# adc_dac_main6.net
KiCad netlist of a schematic drawn in Altium Designer
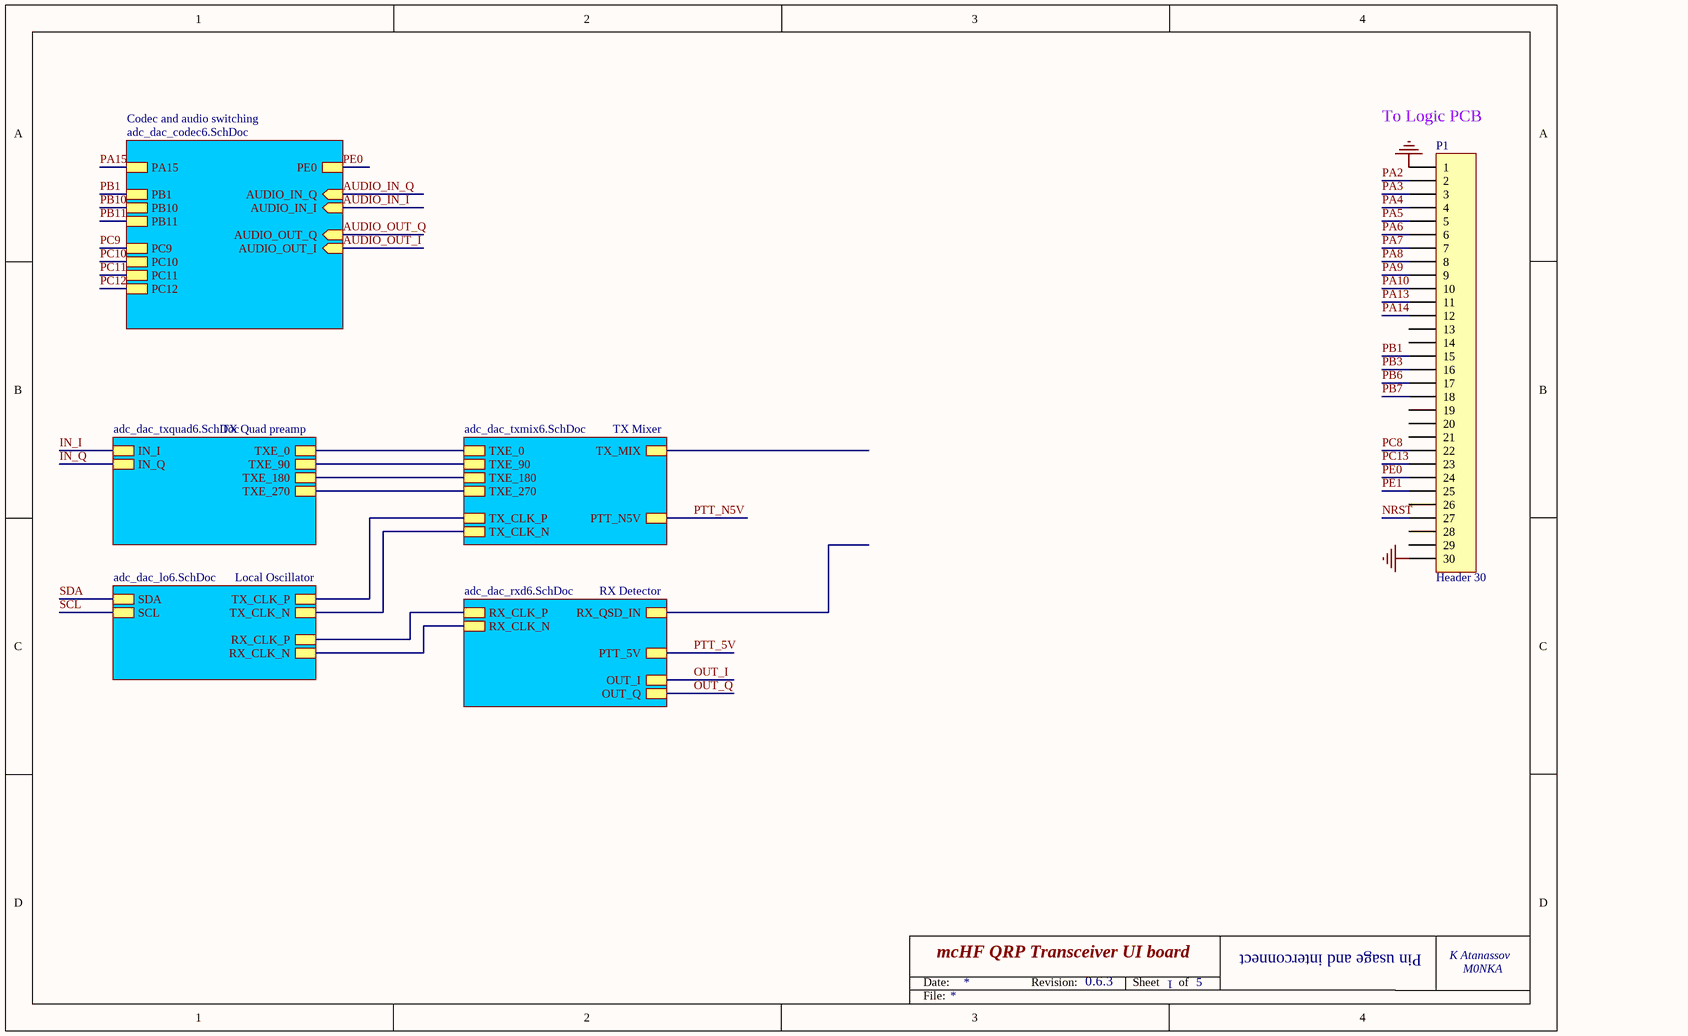
[diagram p0: adc_dac_main6.SchDoc]

(export (version "E")
  (design (tool "Eeschema 10.0.6"))
  (components
    (comp (ref "P1")
      (value "Header 30")
      (footprint "HDR1X30")
      (description "Header, 30-Pin")
      (libsource (lib "mcHF_ui") (part "Header 30"))
    )
  )
  (nets
    (net (code "7") (name "/NRST") (class "Default")
      (node (ref "P1") (pin "27") (pinfunction "27_27") (pintype "passive"))
    )
    (net (code "10") (name "/PA2") (class "Default")
      (node (ref "P1") (pin "2") (pinfunction "2_2") (pintype "passive"))
    )
    (net (code "11") (name "/PA3") (class "Default")
      (node (ref "P1") (pin "3") (pinfunction "3_3") (pintype "passive"))
    )
    (net (code "12") (name "/PA4") (class "Default")
      (node (ref "P1") (pin "4") (pinfunction "4_4") (pintype "passive"))
    )
    (net (code "13") (name "/PA5") (class "Default")
      (node (ref "P1") (pin "5") (pinfunction "5_5") (pintype "passive"))
    )
    (net (code "14") (name "/PA6") (class "Default")
      (node (ref "P1") (pin "6") (pinfunction "6_6") (pintype "passive"))
    )
    (net (code "15") (name "/PA7") (class "Default")
      (node (ref "P1") (pin "7") (pinfunction "7_7") (pintype "passive"))
    )
    (net (code "16") (name "/PA8") (class "Default")
      (node (ref "P1") (pin "8") (pinfunction "8_8") (pintype "passive"))
    )
    (net (code "17") (name "/PA9") (class "Default")
      (node (ref "P1") (pin "9") (pinfunction "9_9") (pintype "passive"))
    )
    (net (code "18") (name "/PA10") (class "Default")
      (node (ref "P1") (pin "10") (pinfunction "10_10") (pintype "passive"))
    )
    (net (code "19") (name "/PA13") (class "Default")
      (node (ref "P1") (pin "11") (pinfunction "11_11") (pintype "passive"))
    )
    (net (code "20") (name "/PA14") (class "Default")
      (node (ref "P1") (pin "12") (pinfunction "12_12") (pintype "passive"))
    )
    (net (code "22") (name "/PB1") (class "Default")
      (node (ref "P1") (pin "15") (pinfunction "15_15") (pintype "passive"))
    )
    (net (code "23") (name "/PB3") (class "Default")
      (node (ref "P1") (pin "16") (pinfunction "16_16") (pintype "passive"))
    )
    (net (code "24") (name "/PB6") (class "Default")
      (node (ref "P1") (pin "17") (pinfunction "17_17") (pintype "passive"))
    )
    (net (code "25") (name "/PB7") (class "Default")
      (node (ref "P1") (pin "18") (pinfunction "18_18") (pintype "passive"))
    )
    (net (code "28") (name "/PC8") (class "Default")
      (node (ref "P1") (pin "22") (pinfunction "22_22") (pintype "passive"))
    )
    (net (code "33") (name "/PC13") (class "Default")
      (node (ref "P1") (pin "23") (pinfunction "23_23") (pintype "passive"))
    )
    (net (code "34") (name "/PE0") (class "Default")
      (node (ref "P1") (pin "24") (pinfunction "24_24") (pintype "passive"))
    )
    (net (code "35") (name "/PE1") (class "Default")
      (node (ref "P1") (pin "25") (pinfunction "25_25") (pintype "passive"))
    )
    (net (code "50") (name "GND") (class "Default")
      (node (ref "P1") (pin "1") (pinfunction "1_1") (pintype "passive"))
      (node (ref "P1") (pin "30") (pinfunction "30_30") (pintype "passive"))
    )
    (net (code "51") (name "unconnected-(P1-Pad13)") (class "Default")
      (node (ref "P1") (pin "13") (pinfunction "13_13") (pintype "passive"))
    )
    (net (code "52") (name "unconnected-(P1-Pad14)") (class "Default")
      (node (ref "P1") (pin "14") (pinfunction "14_14") (pintype "passive"))
    )
    (net (code "53") (name "unconnected-(P1-Pad19)") (class "Default")
      (node (ref "P1") (pin "19") (pinfunction "19_19") (pintype "passive"))
    )
    (net (code "54") (name "unconnected-(P1-Pad20)") (class "Default")
      (node (ref "P1") (pin "20") (pinfunction "20_20") (pintype "passive"))
    )
    (net (code "55") (name "unconnected-(P1-Pad21)") (class "Default")
      (node (ref "P1") (pin "21") (pinfunction "21_21") (pintype "passive"))
    )
    (net (code "56") (name "unconnected-(P1-Pad26)") (class "Default")
      (node (ref "P1") (pin "26") (pinfunction "26_26") (pintype "passive"))
    )
    (net (code "57") (name "unconnected-(P1-Pad28)") (class "Default")
      (node (ref "P1") (pin "28") (pinfunction "28_28") (pintype "passive"))
    )
    (net (code "58") (name "unconnected-(P1-Pad29)") (class "Default")
      (node (ref "P1") (pin "29") (pinfunction "29_29") (pintype "passive"))
    )
  )
)
